# p1.net
KiCad netlist of a schematic drawn in EAGLE
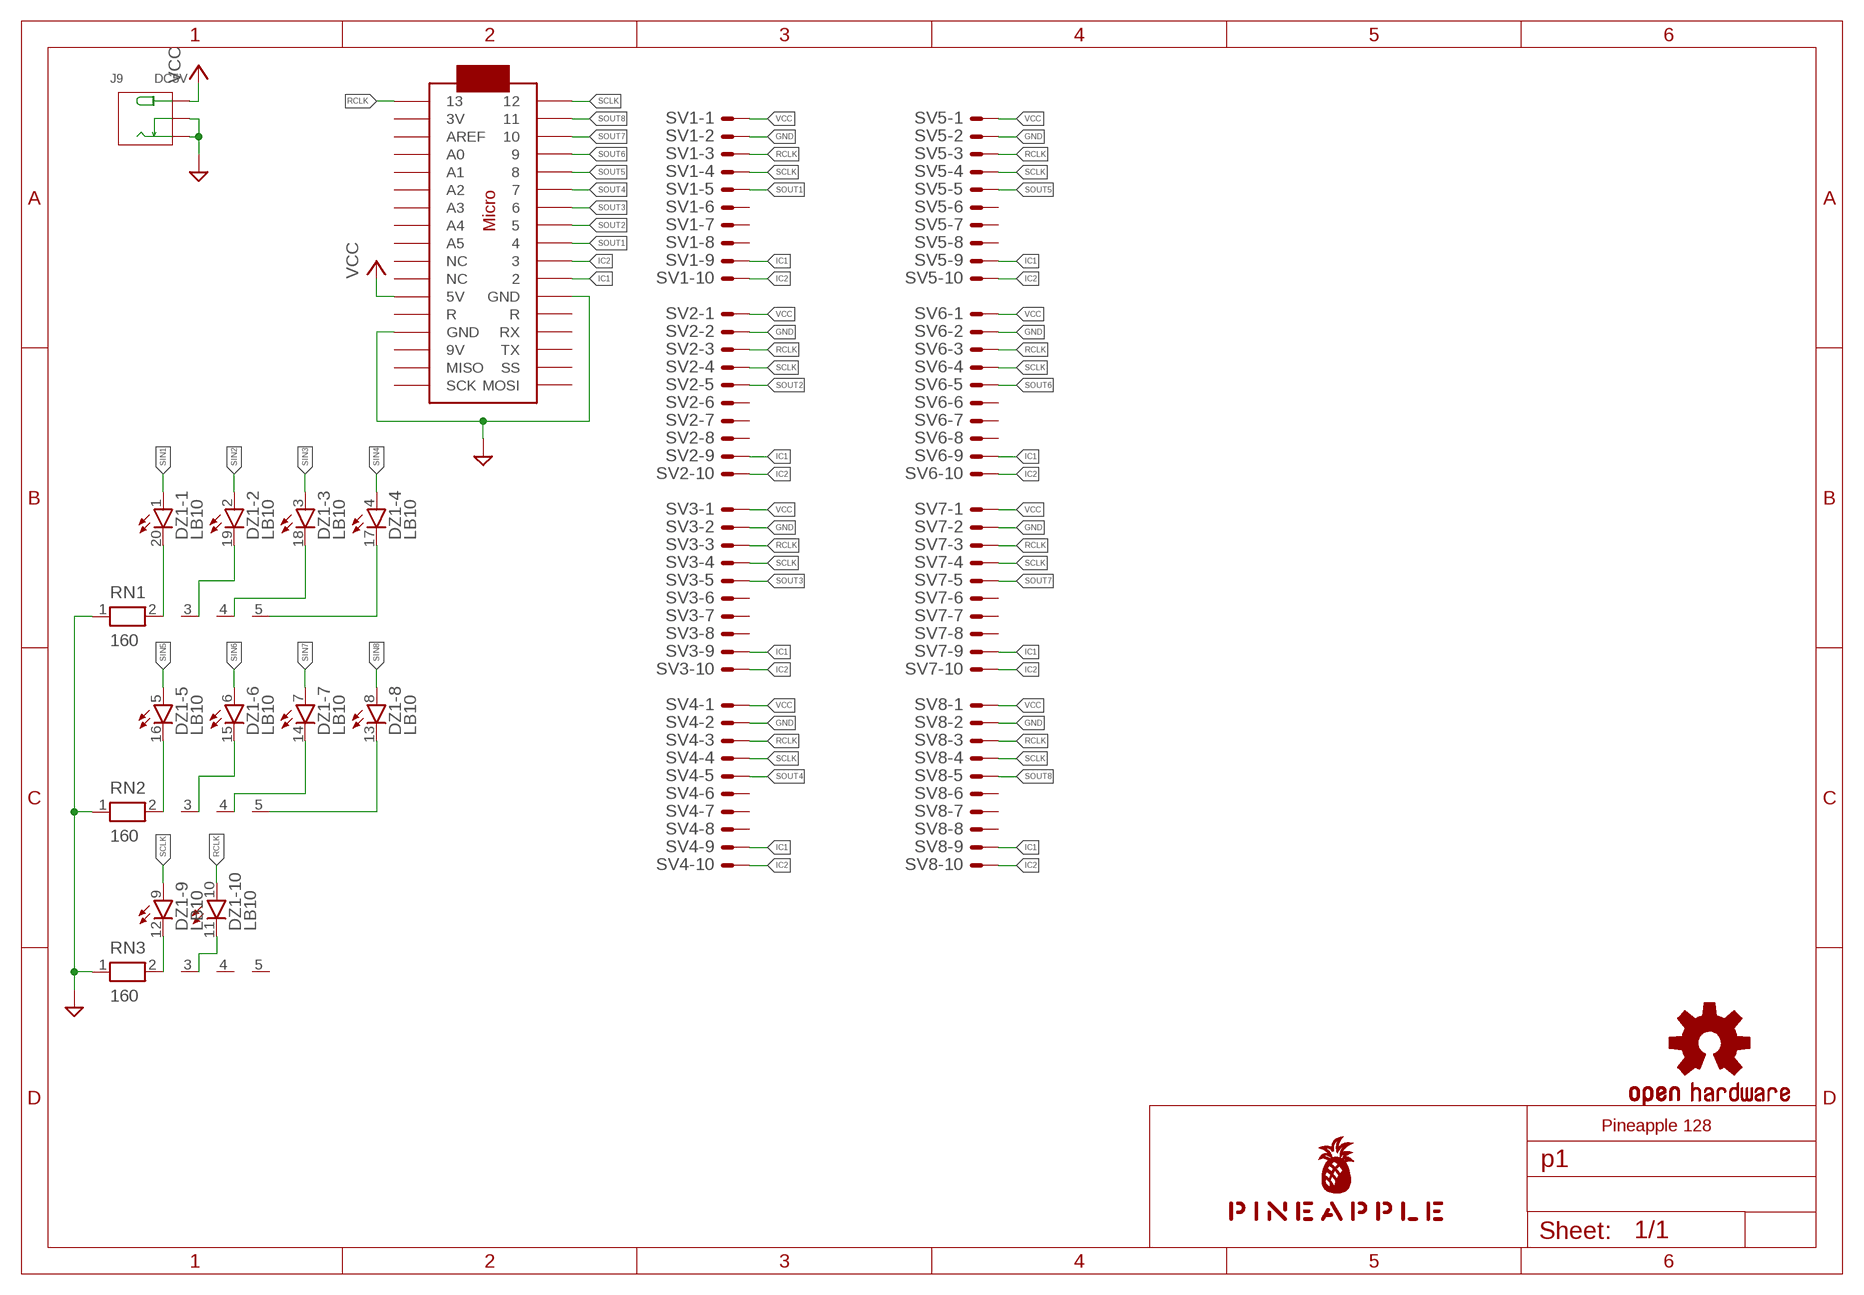
[diagram p0: schematic, sheet 1]

(export (version "E")
  (design (tool "Eeschema 10.0.6"))
  (components
    (comp (ref "DZ1")
      (value "LB10")
      (footprint "eagle-import:LB10")
      (libsource (lib "eagle-import") (part "LB10"))
    )
    (comp (ref "J9")
      (value "DC5V")
      (footprint "eagle-import:3P-L14.2_W11.0_H9.0MM")
      (libsource (lib "eagle-import") (part "JACK-DC-005'DC-005'"))
    )
    (comp (ref "LOGO1")
      (value "OSHW-LOGOS-COPPER")
      (footprint "eagle-import:OSHW-LOGO-S_COPPER")
      (libsource (lib "eagle-import") (part "OSHW-LOGOS-COPPER"))
    )
    (comp (ref "RN1")
      (value "160")
      (footprint "eagle-import:RN-5")
      (libsource (lib "eagle-import") (part "RN04"))
    )
    (comp (ref "RN2")
      (value "160")
      (footprint "eagle-import:RN-5")
      (libsource (lib "eagle-import") (part "RN04"))
    )
    (comp (ref "RN3")
      (value "160")
      (footprint "eagle-import:RN-5")
      (libsource (lib "eagle-import") (part "RN04"))
    )
    (comp (ref "SV1")
      (value "ML10E")
      (footprint "eagle-import:ML10")
      (libsource (lib "eagle-import") (part "ML10E"))
    )
    (comp (ref "SV2")
      (value "ML10E")
      (footprint "eagle-import:ML10")
      (libsource (lib "eagle-import") (part "ML10E"))
    )
    (comp (ref "SV3")
      (value "ML10E")
      (footprint "eagle-import:ML10")
      (libsource (lib "eagle-import") (part "ML10E"))
    )
    (comp (ref "SV4")
      (value "ML10E")
      (footprint "eagle-import:ML10")
      (libsource (lib "eagle-import") (part "ML10E"))
    )
    (comp (ref "SV5")
      (value "ML10E")
      (footprint "eagle-import:ML10")
      (libsource (lib "eagle-import") (part "ML10E"))
    )
    (comp (ref "SV6")
      (value "ML10E")
      (footprint "eagle-import:ML10")
      (libsource (lib "eagle-import") (part "ML10E"))
    )
    (comp (ref "SV7")
      (value "ML10E")
      (footprint "eagle-import:ML10")
      (libsource (lib "eagle-import") (part "ML10E"))
    )
    (comp (ref "SV8")
      (value "ML10E")
      (footprint "eagle-import:ML10")
      (libsource (lib "eagle-import") (part "ML10E"))
    )
    (comp (ref "U$1")
      (value "PINEAPPLE450_SILK")
      (footprint "eagle-import:PINEAPPLE450_SILK")
      (libsource (lib "eagle-import") (part "PINEAPPLE450_SILK"))
    )
    (comp (ref "U$2")
      (value "ARDUINOMICRO")
      (footprint "eagle-import:ARDUINOMICRO")
      (libsource (lib "eagle-import") (part "ARDUINOMICRO"))
    )
  )
  (nets
    (net (code "1") (name "GND") (class "Default")
      (node (ref "J9") (pin "-1") (pinfunction "-_-1") (pintype "bidirectional"))
      (node (ref "J9") (pin "-2") (pinfunction "CDN_-2") (pintype "bidirectional"))
      (node (ref "RN1") (pin "1") (pinfunction "1_1") (pintype "passive"))
      (node (ref "RN2") (pin "1") (pinfunction "1_1") (pintype "passive"))
      (node (ref "RN3") (pin "1") (pinfunction "1_1") (pintype "passive"))
      (node (ref "SV1") (pin "2") (pinfunction "S_2") (pintype "passive"))
      (node (ref "SV2") (pin "2") (pinfunction "S_2") (pintype "passive"))
      (node (ref "SV3") (pin "2") (pinfunction "S_2") (pintype "passive"))
      (node (ref "SV4") (pin "2") (pinfunction "S_2") (pintype "passive"))
      (node (ref "SV5") (pin "2") (pinfunction "S_2") (pintype "passive"))
      (node (ref "SV6") (pin "2") (pinfunction "S_2") (pintype "passive"))
      (node (ref "SV7") (pin "2") (pinfunction "S_2") (pintype "passive"))
      (node (ref "SV8") (pin "2") (pinfunction "S_2") (pintype "passive"))
      (node (ref "U$2") (pin "P$12") (pinfunction "GND_P$12") (pintype "bidirectional"))
      (node (ref "U$2") (pin "P$21") (pinfunction "GND_P$21") (pintype "bidirectional"))
    )
    (net (code "2") (name "IC1") (class "Default")
      (node (ref "SV1") (pin "9") (pinfunction "S_9") (pintype "passive"))
      (node (ref "SV2") (pin "9") (pinfunction "S_9") (pintype "passive"))
      (node (ref "SV3") (pin "9") (pinfunction "S_9") (pintype "passive"))
      (node (ref "SV4") (pin "9") (pinfunction "S_9") (pintype "passive"))
      (node (ref "SV5") (pin "9") (pinfunction "S_9") (pintype "passive"))
      (node (ref "SV6") (pin "9") (pinfunction "S_9") (pintype "passive"))
      (node (ref "SV7") (pin "9") (pinfunction "S_9") (pintype "passive"))
      (node (ref "SV8") (pin "9") (pinfunction "S_9") (pintype "passive"))
      (node (ref "U$2") (pin "P$11") (pinfunction "2_P$11") (pintype "bidirectional"))
    )
    (net (code "3") (name "IC2") (class "Default")
      (node (ref "SV1") (pin "10") (pinfunction "S_10") (pintype "passive"))
      (node (ref "SV2") (pin "10") (pinfunction "S_10") (pintype "passive"))
      (node (ref "SV3") (pin "10") (pinfunction "S_10") (pintype "passive"))
      (node (ref "SV4") (pin "10") (pinfunction "S_10") (pintype "passive"))
      (node (ref "SV5") (pin "10") (pinfunction "S_10") (pintype "passive"))
      (node (ref "SV6") (pin "10") (pinfunction "S_10") (pintype "passive"))
      (node (ref "SV7") (pin "10") (pinfunction "S_10") (pintype "passive"))
      (node (ref "SV8") (pin "10") (pinfunction "S_10") (pintype "passive"))
      (node (ref "U$2") (pin "P$10") (pinfunction "3_P$10") (pintype "bidirectional"))
    )
    (net (code "4") (name "Net-(DZ1A-C)") (class "Default")
      (node (ref "DZ1") (pin "20") (pinfunction "C_20") (pintype "passive"))
      (node (ref "RN1") (pin "2") (pinfunction "2_2") (pintype "passive"))
    )
    (net (code "5") (name "Net-(DZ1B-C)") (class "Default")
      (node (ref "DZ1") (pin "11") (pinfunction "C_11") (pintype "passive"))
      (node (ref "RN3") (pin "3") (pinfunction "3_3") (pintype "passive"))
    )
    (net (code "6") (name "Net-(DZ1C-C)") (class "Default")
      (node (ref "DZ1") (pin "19") (pinfunction "C_19") (pintype "passive"))
      (node (ref "RN1") (pin "3") (pinfunction "3_3") (pintype "passive"))
    )
    (net (code "7") (name "Net-(DZ1D-C)") (class "Default")
      (node (ref "DZ1") (pin "18") (pinfunction "C_18") (pintype "passive"))
      (node (ref "RN1") (pin "4") (pinfunction "4_4") (pintype "passive"))
    )
    (net (code "8") (name "Net-(DZ1E-C)") (class "Default")
      (node (ref "DZ1") (pin "17") (pinfunction "C_17") (pintype "passive"))
      (node (ref "RN1") (pin "5") (pinfunction "5_5") (pintype "passive"))
    )
    (net (code "9") (name "Net-(DZ1F-C)") (class "Default")
      (node (ref "DZ1") (pin "16") (pinfunction "C_16") (pintype "passive"))
      (node (ref "RN2") (pin "2") (pinfunction "2_2") (pintype "passive"))
    )
    (net (code "10") (name "Net-(DZ1G-C)") (class "Default")
      (node (ref "DZ1") (pin "15") (pinfunction "C_15") (pintype "passive"))
      (node (ref "RN2") (pin "3") (pinfunction "3_3") (pintype "passive"))
    )
    (net (code "11") (name "Net-(DZ1H-C)") (class "Default")
      (node (ref "DZ1") (pin "14") (pinfunction "C_14") (pintype "passive"))
      (node (ref "RN2") (pin "4") (pinfunction "4_4") (pintype "passive"))
    )
    (net (code "12") (name "Net-(DZ1I-C)") (class "Default")
      (node (ref "DZ1") (pin "13") (pinfunction "C_13") (pintype "passive"))
      (node (ref "RN2") (pin "5") (pinfunction "5_5") (pintype "passive"))
    )
    (net (code "13") (name "Net-(DZ1J-C)") (class "Default")
      (node (ref "DZ1") (pin "12") (pinfunction "C_12") (pintype "passive"))
      (node (ref "RN3") (pin "2") (pinfunction "2_2") (pintype "passive"))
    )
    (net (code "14") (name "RCLK") (class "Default")
      (node (ref "DZ1") (pin "10") (pinfunction "A_10") (pintype "passive"))
      (node (ref "SV1") (pin "3") (pinfunction "S_3") (pintype "passive"))
      (node (ref "SV2") (pin "3") (pinfunction "S_3") (pintype "passive"))
      (node (ref "SV3") (pin "3") (pinfunction "S_3") (pintype "passive"))
      (node (ref "SV4") (pin "3") (pinfunction "S_3") (pintype "passive"))
      (node (ref "SV5") (pin "3") (pinfunction "S_3") (pintype "passive"))
      (node (ref "SV6") (pin "3") (pinfunction "S_3") (pintype "passive"))
      (node (ref "SV7") (pin "3") (pinfunction "S_3") (pintype "passive"))
      (node (ref "SV8") (pin "3") (pinfunction "S_3") (pintype "passive"))
      (node (ref "U$2") (pin "P$34") (pinfunction "13_P$34") (pintype "bidirectional"))
    )
    (net (code "15") (name "SCLK") (class "Default")
      (node (ref "DZ1") (pin "9") (pinfunction "A_9") (pintype "passive"))
      (node (ref "SV1") (pin "4") (pinfunction "S_4") (pintype "passive"))
      (node (ref "SV2") (pin "4") (pinfunction "S_4") (pintype "passive"))
      (node (ref "SV3") (pin "4") (pinfunction "S_4") (pintype "passive"))
      (node (ref "SV4") (pin "4") (pinfunction "S_4") (pintype "passive"))
      (node (ref "SV5") (pin "4") (pinfunction "S_4") (pintype "passive"))
      (node (ref "SV6") (pin "4") (pinfunction "S_4") (pintype "passive"))
      (node (ref "SV7") (pin "4") (pinfunction "S_4") (pintype "passive"))
      (node (ref "SV8") (pin "4") (pinfunction "S_4") (pintype "passive"))
      (node (ref "U$2") (pin "P$1") (pinfunction "12_P$1") (pintype "bidirectional"))
    )
    (net (code "16") (name "SIN1") (class "Default")
      (node (ref "DZ1") (pin "1") (pinfunction "A_1") (pintype "passive"))
    )
    (net (code "17") (name "SIN2") (class "Default")
      (node (ref "DZ1") (pin "2") (pinfunction "A_2") (pintype "passive"))
    )
    (net (code "18") (name "SIN3") (class "Default")
      (node (ref "DZ1") (pin "3") (pinfunction "A_3") (pintype "passive"))
    )
    (net (code "19") (name "SIN4") (class "Default")
      (node (ref "DZ1") (pin "4") (pinfunction "A_4") (pintype "passive"))
    )
    (net (code "20") (name "SIN5") (class "Default")
      (node (ref "DZ1") (pin "5") (pinfunction "A_5") (pintype "passive"))
    )
    (net (code "21") (name "SIN6") (class "Default")
      (node (ref "DZ1") (pin "6") (pinfunction "A_6") (pintype "passive"))
    )
    (net (code "22") (name "SIN7") (class "Default")
      (node (ref "DZ1") (pin "7") (pinfunction "A_7") (pintype "passive"))
    )
    (net (code "23") (name "SIN8") (class "Default")
      (node (ref "DZ1") (pin "8") (pinfunction "A_8") (pintype "passive"))
    )
    (net (code "24") (name "SOUT1") (class "Default")
      (node (ref "SV1") (pin "5") (pinfunction "S_5") (pintype "passive"))
      (node (ref "U$2") (pin "P$9") (pinfunction "4_P$9") (pintype "bidirectional"))
    )
    (net (code "25") (name "SOUT2") (class "Default")
      (node (ref "SV2") (pin "5") (pinfunction "S_5") (pintype "passive"))
      (node (ref "U$2") (pin "P$8") (pinfunction "5_P$8") (pintype "bidirectional"))
    )
    (net (code "26") (name "SOUT3") (class "Default")
      (node (ref "SV3") (pin "5") (pinfunction "S_5") (pintype "passive"))
      (node (ref "U$2") (pin "P$7") (pinfunction "6_P$7") (pintype "bidirectional"))
    )
    (net (code "27") (name "SOUT4") (class "Default")
      (node (ref "SV4") (pin "5") (pinfunction "S_5") (pintype "passive"))
      (node (ref "U$2") (pin "P$6") (pinfunction "7_P$6") (pintype "bidirectional"))
    )
    (net (code "28") (name "SOUT5") (class "Default")
      (node (ref "SV5") (pin "5") (pinfunction "S_5") (pintype "passive"))
      (node (ref "U$2") (pin "P$5") (pinfunction "8_P$5") (pintype "bidirectional"))
    )
    (net (code "29") (name "SOUT6") (class "Default")
      (node (ref "SV6") (pin "5") (pinfunction "S_5") (pintype "passive"))
      (node (ref "U$2") (pin "P$4") (pinfunction "9_P$4") (pintype "bidirectional"))
    )
    (net (code "30") (name "SOUT7") (class "Default")
      (node (ref "SV7") (pin "5") (pinfunction "S_5") (pintype "passive"))
      (node (ref "U$2") (pin "P$3") (pinfunction "10_P$3") (pintype "bidirectional"))
    )
    (net (code "31") (name "SOUT8") (class "Default")
      (node (ref "SV8") (pin "5") (pinfunction "S_5") (pintype "passive"))
      (node (ref "U$2") (pin "P$2") (pinfunction "11_P$2") (pintype "bidirectional"))
    )
    (net (code "32") (name "VCC") (class "Default")
      (node (ref "J9") (pin "+") (pinfunction "+_+") (pintype "bidirectional"))
      (node (ref "SV1") (pin "1") (pinfunction "S_1") (pintype "passive"))
      (node (ref "SV2") (pin "1") (pinfunction "S_1") (pintype "passive"))
      (node (ref "SV3") (pin "1") (pinfunction "S_1") (pintype "passive"))
      (node (ref "SV4") (pin "1") (pinfunction "S_1") (pintype "passive"))
      (node (ref "SV5") (pin "1") (pinfunction "S_1") (pintype "passive"))
      (node (ref "SV6") (pin "1") (pinfunction "S_1") (pintype "passive"))
      (node (ref "SV7") (pin "1") (pinfunction "S_1") (pintype "passive"))
      (node (ref "SV8") (pin "1") (pinfunction "S_1") (pintype "passive"))
      (node (ref "U$2") (pin "P$23") (pinfunction "5V_P$23") (pintype "bidirectional"))
    )
    (net (code "33") (name "unconnected-(RN3-Pad4)") (class "Default")
      (node (ref "RN3") (pin "4") (pinfunction "4_4") (pintype "passive"))
    )
    (net (code "34") (name "unconnected-(RN3-Pad5)") (class "Default")
      (node (ref "RN3") (pin "5") (pinfunction "5_5") (pintype "passive"))
    )
    (net (code "35") (name "unconnected-(SV1G-S-Pad6)") (class "Default")
      (node (ref "SV1") (pin "6") (pinfunction "S_6") (pintype "passive"))
    )
    (net (code "36") (name "unconnected-(SV1H-S-Pad7)") (class "Default")
      (node (ref "SV1") (pin "7") (pinfunction "S_7") (pintype "passive"))
    )
    (net (code "37") (name "unconnected-(SV1I-S-Pad8)") (class "Default")
      (node (ref "SV1") (pin "8") (pinfunction "S_8") (pintype "passive"))
    )
    (net (code "38") (name "unconnected-(SV2G-S-Pad6)") (class "Default")
      (node (ref "SV2") (pin "6") (pinfunction "S_6") (pintype "passive"))
    )
    (net (code "39") (name "unconnected-(SV2H-S-Pad7)") (class "Default")
      (node (ref "SV2") (pin "7") (pinfunction "S_7") (pintype "passive"))
    )
    (net (code "40") (name "unconnected-(SV2I-S-Pad8)") (class "Default")
      (node (ref "SV2") (pin "8") (pinfunction "S_8") (pintype "passive"))
    )
    (net (code "41") (name "unconnected-(SV3G-S-Pad6)") (class "Default")
      (node (ref "SV3") (pin "6") (pinfunction "S_6") (pintype "passive"))
    )
    (net (code "42") (name "unconnected-(SV3H-S-Pad7)") (class "Default")
      (node (ref "SV3") (pin "7") (pinfunction "S_7") (pintype "passive"))
    )
    (net (code "43") (name "unconnected-(SV3I-S-Pad8)") (class "Default")
      (node (ref "SV3") (pin "8") (pinfunction "S_8") (pintype "passive"))
    )
    (net (code "44") (name "unconnected-(SV4G-S-Pad6)") (class "Default")
      (node (ref "SV4") (pin "6") (pinfunction "S_6") (pintype "passive"))
    )
    (net (code "45") (name "unconnected-(SV4H-S-Pad7)") (class "Default")
      (node (ref "SV4") (pin "7") (pinfunction "S_7") (pintype "passive"))
    )
    (net (code "46") (name "unconnected-(SV4I-S-Pad8)") (class "Default")
      (node (ref "SV4") (pin "8") (pinfunction "S_8") (pintype "passive"))
    )
    (net (code "47") (name "unconnected-(SV5G-S-Pad6)") (class "Default")
      (node (ref "SV5") (pin "6") (pinfunction "S_6") (pintype "passive"))
    )
    (net (code "48") (name "unconnected-(SV5H-S-Pad7)") (class "Default")
      (node (ref "SV5") (pin "7") (pinfunction "S_7") (pintype "passive"))
    )
    (net (code "49") (name "unconnected-(SV5I-S-Pad8)") (class "Default")
      (node (ref "SV5") (pin "8") (pinfunction "S_8") (pintype "passive"))
    )
    (net (code "50") (name "unconnected-(SV6G-S-Pad6)") (class "Default")
      (node (ref "SV6") (pin "6") (pinfunction "S_6") (pintype "passive"))
    )
    (net (code "51") (name "unconnected-(SV6H-S-Pad7)") (class "Default")
      (node (ref "SV6") (pin "7") (pinfunction "S_7") (pintype "passive"))
    )
    (net (code "52") (name "unconnected-(SV6I-S-Pad8)") (class "Default")
      (node (ref "SV6") (pin "8") (pinfunction "S_8") (pintype "passive"))
    )
    (net (code "53") (name "unconnected-(SV7G-S-Pad6)") (class "Default")
      (node (ref "SV7") (pin "6") (pinfunction "S_6") (pintype "passive"))
    )
    (net (code "54") (name "unconnected-(SV7H-S-Pad7)") (class "Default")
      (node (ref "SV7") (pin "7") (pinfunction "S_7") (pintype "passive"))
    )
    (net (code "55") (name "unconnected-(SV7I-S-Pad8)") (class "Default")
      (node (ref "SV7") (pin "8") (pinfunction "S_8") (pintype "passive"))
    )
    (net (code "56") (name "unconnected-(SV8G-S-Pad6)") (class "Default")
      (node (ref "SV8") (pin "6") (pinfunction "S_6") (pintype "passive"))
    )
    (net (code "57") (name "unconnected-(SV8H-S-Pad7)") (class "Default")
      (node (ref "SV8") (pin "7") (pinfunction "S_7") (pintype "passive"))
    )
    (net (code "58") (name "unconnected-(SV8I-S-Pad8)") (class "Default")
      (node (ref "SV8") (pin "8") (pinfunction "S_8") (pintype "passive"))
    )
    (net (code "59") (name "unconnected-(U$2-3V-PadP$33)") (class "Default")
      (node (ref "U$2") (pin "P$33") (pinfunction "3V_P$33") (pintype "bidirectional"))
    )
    (net (code "60") (name "unconnected-(U$2-9V-PadP$20)") (class "Default")
      (node (ref "U$2") (pin "P$20") (pinfunction "9V_P$20") (pintype "bidirectional"))
    )
    (net (code "61") (name "unconnected-(U$2-A0-PadP$31)") (class "Default")
      (node (ref "U$2") (pin "P$31") (pinfunction "A0_P$31") (pintype "bidirectional"))
    )
    (net (code "62") (name "unconnected-(U$2-A1-PadP$30)") (class "Default")
      (node (ref "U$2") (pin "P$30") (pinfunction "A1_P$30") (pintype "bidirectional"))
    )
    (net (code "63") (name "unconnected-(U$2-A2-PadP$29)") (class "Default")
      (node (ref "U$2") (pin "P$29") (pinfunction "A2_P$29") (pintype "bidirectional"))
    )
    (net (code "64") (name "unconnected-(U$2-A3-PadP$28)") (class "Default")
      (node (ref "U$2") (pin "P$28") (pinfunction "A3_P$28") (pintype "bidirectional"))
    )
    (net (code "65") (name "unconnected-(U$2-A4-PadP$27)") (class "Default")
      (node (ref "U$2") (pin "P$27") (pinfunction "A4_P$27") (pintype "bidirectional"))
    )
    (net (code "66") (name "unconnected-(U$2-A5-PadP$26)") (class "Default")
      (node (ref "U$2") (pin "P$26") (pinfunction "A5_P$26") (pintype "bidirectional"))
    )
    (net (code "67") (name "unconnected-(U$2-AREF-PadP$32)") (class "Default")
      (node (ref "U$2") (pin "P$32") (pinfunction "AREF_P$32") (pintype "bidirectional"))
    )
    (net (code "68") (name "unconnected-(U$2-MISO-PadP$19)") (class "Default")
      (node (ref "U$2") (pin "P$19") (pinfunction "MISO_P$19") (pintype "bidirectional"))
    )
    (net (code "69") (name "unconnected-(U$2-MOSI-PadP$17)") (class "Default")
      (node (ref "U$2") (pin "P$17") (pinfunction "MOSI_P$17") (pintype "bidirectional"))
    )
    (net (code "70") (name "unconnected-(U$2-NC-PadP$24)") (class "Default")
      (node (ref "U$2") (pin "P$24") (pinfunction "NC_P$24") (pintype "bidirectional"))
    )
    (net (code "71") (name "unconnected-(U$2-NC-PadP$25)") (class "Default")
      (node (ref "U$2") (pin "P$25") (pinfunction "NC_P$25") (pintype "bidirectional"))
    )
    (net (code "72") (name "unconnected-(U$2-R-PadP$13)") (class "Default")
      (node (ref "U$2") (pin "P$13") (pinfunction "R_P$13") (pintype "bidirectional"))
    )
    (net (code "73") (name "unconnected-(U$2-R-PadP$22)") (class "Default")
      (node (ref "U$2") (pin "P$22") (pinfunction "R_P$22") (pintype "bidirectional"))
    )
    (net (code "74") (name "unconnected-(U$2-RX-PadP$14)") (class "Default")
      (node (ref "U$2") (pin "P$14") (pinfunction "RX_P$14") (pintype "bidirectional"))
    )
    (net (code "75") (name "unconnected-(U$2-SCK-PadP$18)") (class "Default")
      (node (ref "U$2") (pin "P$18") (pinfunction "SCK_P$18") (pintype "bidirectional"))
    )
    (net (code "76") (name "unconnected-(U$2-SS-PadP$16)") (class "Default")
      (node (ref "U$2") (pin "P$16") (pinfunction "SS_P$16") (pintype "bidirectional"))
    )
    (net (code "77") (name "unconnected-(U$2-TX-PadP$15)") (class "Default")
      (node (ref "U$2") (pin "P$15") (pinfunction "TX_P$15") (pintype "bidirectional"))
    )
  )
)
